# QUTMS-BrakeLight-S01-V01.net
KiCad netlist of a schematic drawn in Altium Designer
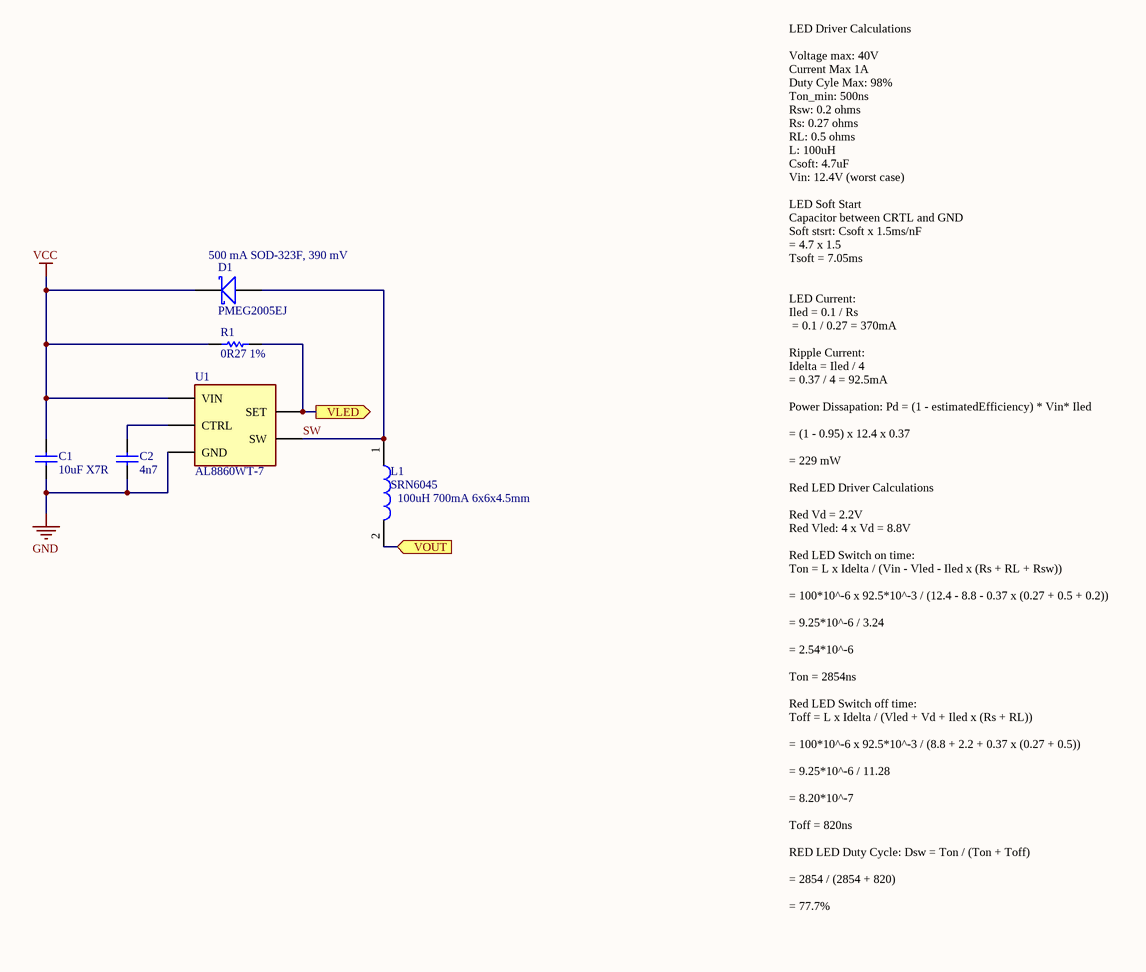
[diagram p0: QUTMS-BrakeLight-S01-V01.SchDoc]

(export (version "E")
  (design (tool "Eeschema 10.0.6"))
  (components
    (comp (ref "C1")
      (value "10uF X7R")
      (footprint "Cap_Ceramic_0603")
      (description "Capacitor, Ceramic, SMD, 10uF, 50V, 5%, X7R, 0603")
      (libsource (lib "StandardCapacitors") (part "10uF 50V 5% X7R 0603"))
    )
    (comp (ref "C2")
      (value "4n7")
      (footprint "Cap_Ceramic_0603")
      (description "Capacitor, Ceramic, SMD, 4n7, 25V, 5%, X7R, 0603")
      (libsource (lib "StandardCapacitors") (part "4n7 25V 5% X7R 0603"))
    )
    (comp (ref "D1")
      (value "PMEG2005EJ")
      (footprint "SOD-323F")
      (description "PMEG2005EJ,115 -  Schottky Rectifier, 20 V, 500 mA, Single, SOD-323F, 2 Pins, 390 mV")
      (libsource (lib "QUTMS_DiodeLibrary") (part "PMEG2005EJ"))
    )
    (comp (ref "L1")
      (value "SRN6045")
      (footprint "Bourns Inductor 6x6x4.5mm")
      (description "Power Inductor (SMD), 100 µH, 700 mA, Semishielded, 800 mA")
      (libsource (lib "QUTMS_InductorLibrary") (part "SRN6045"))
    )
    (comp (ref "R1")
      (value "0R27 1%")
      (footprint "Res_ThinFilm_0603")
      (libsource (lib "StandardResistors") (part "0R27 1% 0603"))
    )
    (comp (ref "U1")
      (value "AL8860WT-7")
      (footprint "TSOT-25")
      (libsource (lib "QUTMS_PowerSupplyLibrary") (part "AL8860WT-7"))
    )
  )
  (nets
    (net (code "1") (name "/SW") (class "Default")
      (node (ref "D1") (pin "A") (pinfunction "Anode_A") (pintype "passive"))
      (node (ref "L1") (pin "1") (pinfunction "1_1") (pintype "passive"))
      (node (ref "U1") (pin "1") (pinfunction "SW_1") (pintype "power_in"))
    )
    (net (code "2") (name "/VLED") (class "Default")
      (node (ref "R1") (pin "2") (pinfunction "2_2") (pintype "passive"))
      (node (ref "U1") (pin "4") (pinfunction "SET_4") (pintype "power_in"))
    )
    (net (code "3") (name "/VOUT") (class "Default")
      (node (ref "L1") (pin "2") (pinfunction "2_2") (pintype "passive"))
    )
    (net (code "4") (name "GND") (class "Default")
      (node (ref "C1") (pin "1") (pinfunction "1_1") (pintype "passive"))
      (node (ref "C2") (pin "1") (pinfunction "1_1") (pintype "passive"))
      (node (ref "U1") (pin "2") (pinfunction "GND_2") (pintype "power_in"))
    )
    (net (code "5") (name "Net-(U1-CTRL)") (class "Default")
      (node (ref "C2") (pin "2") (pinfunction "2_2") (pintype "passive"))
      (node (ref "U1") (pin "3") (pinfunction "CTRL_3") (pintype "power_in"))
    )
    (net (code "6") (name "VCC") (class "Default")
      (node (ref "C1") (pin "2") (pinfunction "2_2") (pintype "passive"))
      (node (ref "D1") (pin "K") (pinfunction "Cathode_K") (pintype "passive"))
      (node (ref "R1") (pin "1") (pinfunction "1_1") (pintype "passive"))
      (node (ref "U1") (pin "5") (pinfunction "VIN_5") (pintype "power_in"))
    )
  )
)
